# learning.net
KiCad netlist of a schematic drawn in EAGLE
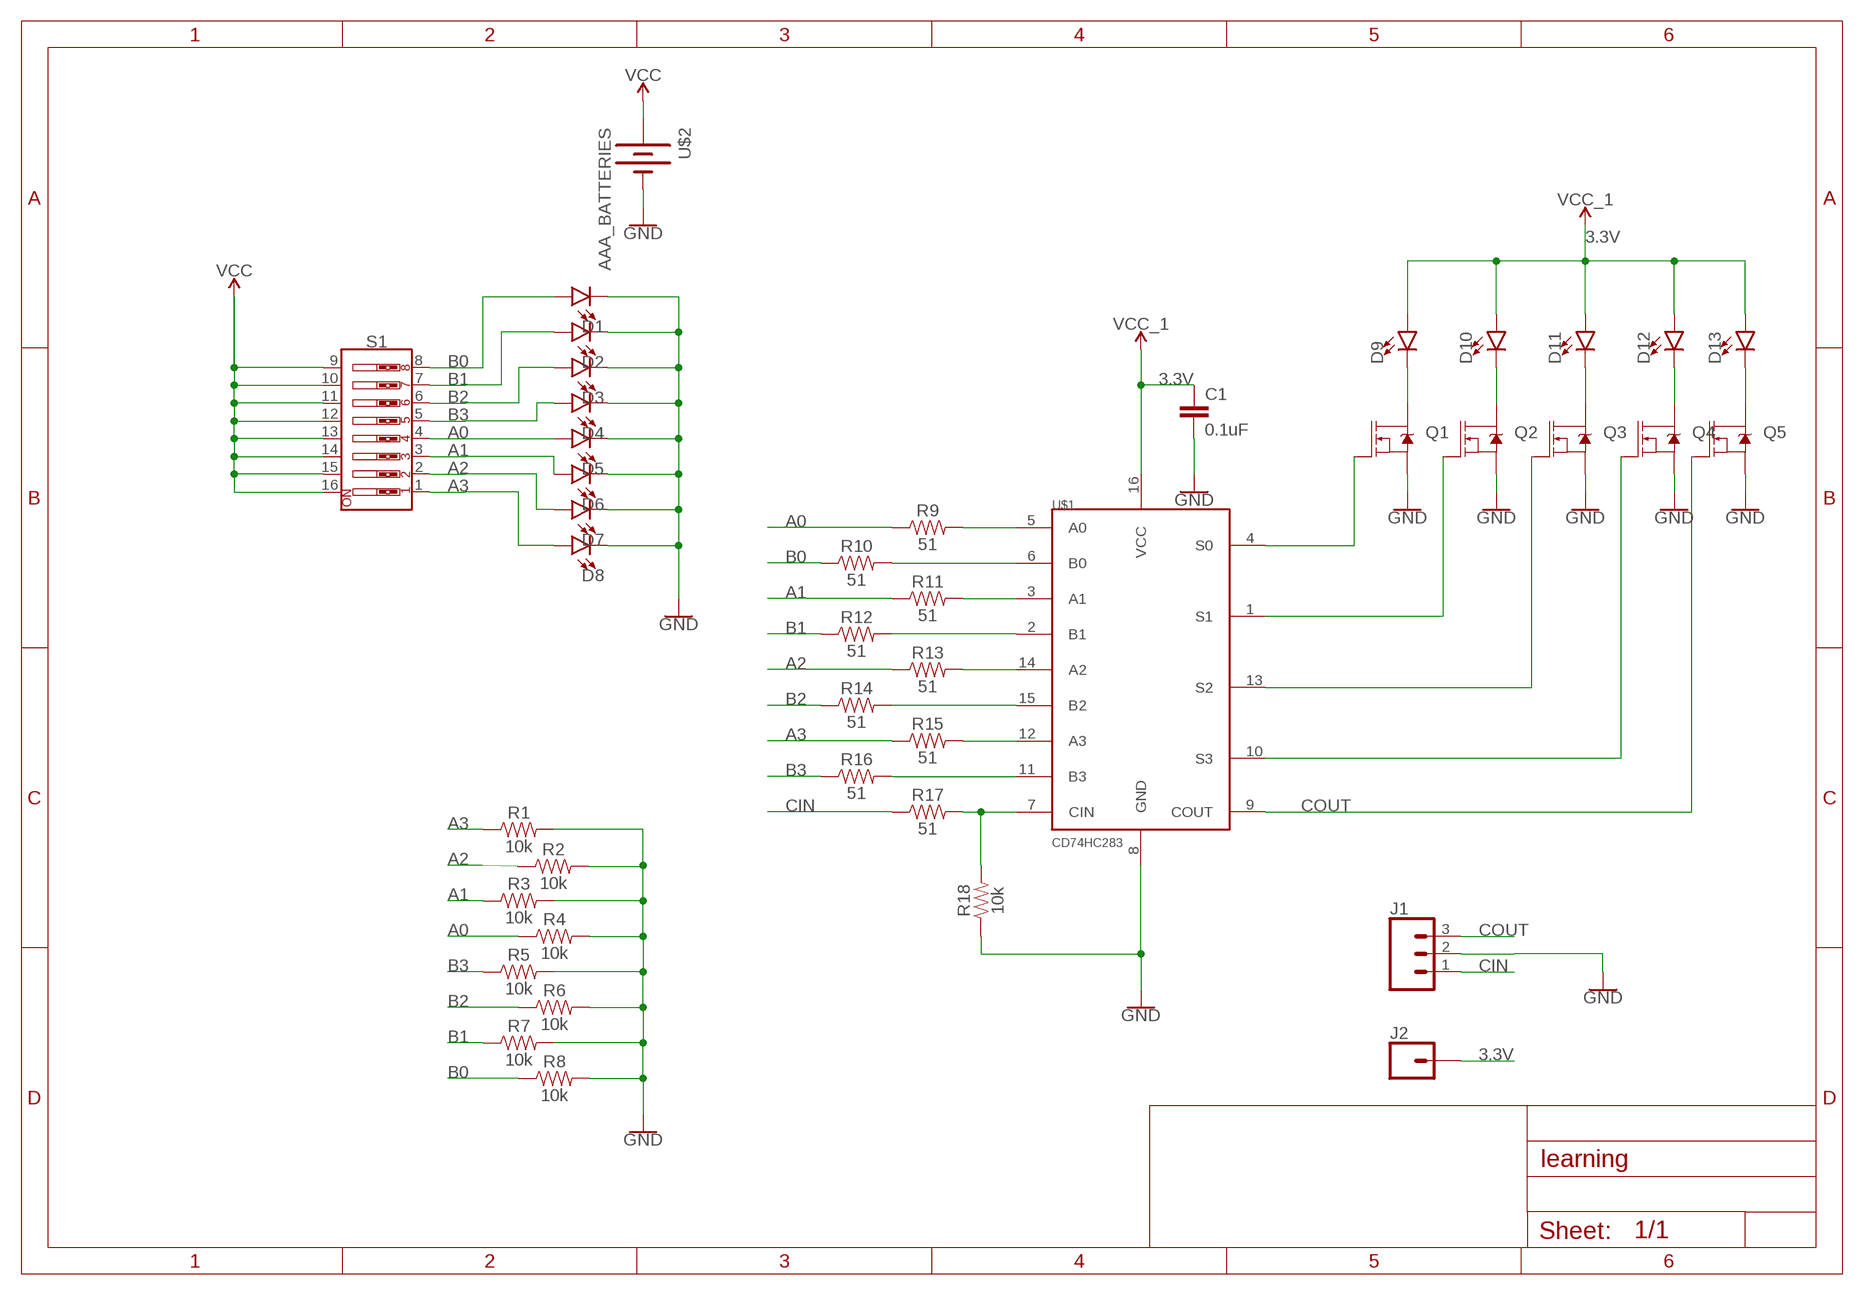
[diagram p0: schematic, sheet 1]

(export (version "E")
  (design (tool "Eeschema 10.0.6"))
  (components
    (comp (ref "C1")
      (value "0.1uF")
      (footprint "eagle-import:0603")
      (libsource (lib "eagle-import") (part "0.1UF-0603-25V-5%"))
    )
    (comp (ref "D1")
      (value "LED5MM")
      (footprint "eagle-import:LED_5MM")
      (libsource (lib "eagle-import") (part "LED5MM"))
    )
    (comp (ref "D2")
      (value "LED5MM")
      (footprint "eagle-import:LED_5MM")
      (libsource (lib "eagle-import") (part "LED5MM"))
    )
    (comp (ref "D3")
      (value "LED5MM")
      (footprint "eagle-import:LED_5MM")
      (libsource (lib "eagle-import") (part "LED5MM"))
    )
    (comp (ref "D4")
      (value "LED5MM")
      (footprint "eagle-import:LED_5MM")
      (libsource (lib "eagle-import") (part "LED5MM"))
    )
    (comp (ref "D5")
      (value "LED5MM")
      (footprint "eagle-import:LED_5MM")
      (libsource (lib "eagle-import") (part "LED5MM"))
    )
    (comp (ref "D6")
      (value "LED5MM")
      (footprint "eagle-import:LED_5MM")
      (libsource (lib "eagle-import") (part "LED5MM"))
    )
    (comp (ref "D7")
      (value "LED5MM")
      (footprint "eagle-import:LED_5MM")
      (libsource (lib "eagle-import") (part "LED5MM"))
    )
    (comp (ref "D8")
      (value "LED5MM")
      (footprint "eagle-import:LED_5MM")
      (libsource (lib "eagle-import") (part "LED5MM"))
    )
    (comp (ref "D9")
      (value "LED5MM")
      (footprint "eagle-import:LED_5MM")
      (libsource (lib "eagle-import") (part "LED5MM"))
    )
    (comp (ref "D10")
      (value "LED5MM")
      (footprint "eagle-import:LED_5MM")
      (libsource (lib "eagle-import") (part "LED5MM"))
    )
    (comp (ref "D11")
      (value "LED5MM")
      (footprint "eagle-import:LED_5MM")
      (libsource (lib "eagle-import") (part "LED5MM"))
    )
    (comp (ref "D12")
      (value "LED5MM")
      (footprint "eagle-import:LED_5MM")
      (libsource (lib "eagle-import") (part "LED5MM"))
    )
    (comp (ref "D13")
      (value "LED5MM")
      (footprint "eagle-import:LED_5MM")
      (libsource (lib "eagle-import") (part "LED5MM"))
    )
    (comp (ref "J1")
      (value "CONN_03")
      (footprint "eagle-import:1X03")
      (libsource (lib "eagle-import") (part "CONN_03"))
    )
    (comp (ref "J2")
      (value "CONN_01")
      (footprint "eagle-import:1X01")
      (libsource (lib "eagle-import") (part "CONN_01"))
    )
    (comp (ref "Q1")
      (value "MOSFET-NCH-BSS138")
      (footprint "eagle-import:SOT23-3")
      (libsource (lib "eagle-import") (part "MOSFET-NCH-BSS138"))
    )
    (comp (ref "Q2")
      (value "MOSFET-NCH-BSS138")
      (footprint "eagle-import:SOT23-3")
      (libsource (lib "eagle-import") (part "MOSFET-NCH-BSS138"))
    )
    (comp (ref "Q3")
      (value "MOSFET-NCH-BSS138")
      (footprint "eagle-import:SOT23-3")
      (libsource (lib "eagle-import") (part "MOSFET-NCH-BSS138"))
    )
    (comp (ref "Q4")
      (value "MOSFET-NCH-BSS138")
      (footprint "eagle-import:SOT23-3")
      (libsource (lib "eagle-import") (part "MOSFET-NCH-BSS138"))
    )
    (comp (ref "Q5")
      (value "MOSFET-NCH-BSS138")
      (footprint "eagle-import:SOT23-3")
      (libsource (lib "eagle-import") (part "MOSFET-NCH-BSS138"))
    )
    (comp (ref "R1")
      (value "10k")
      (footprint "eagle-import:0603")
      (libsource (lib "eagle-import") (part "RESISTOR0603"))
    )
    (comp (ref "R2")
      (value "10k")
      (footprint "eagle-import:0603")
      (libsource (lib "eagle-import") (part "RESISTOR0603"))
    )
    (comp (ref "R3")
      (value "10k")
      (footprint "eagle-import:0603")
      (libsource (lib "eagle-import") (part "RESISTOR0603"))
    )
    (comp (ref "R4")
      (value "10k")
      (footprint "eagle-import:0603")
      (libsource (lib "eagle-import") (part "RESISTOR0603"))
    )
    (comp (ref "R5")
      (value "10k")
      (footprint "eagle-import:0603")
      (libsource (lib "eagle-import") (part "RESISTOR0603"))
    )
    (comp (ref "R6")
      (value "10k")
      (footprint "eagle-import:0603")
      (libsource (lib "eagle-import") (part "RESISTOR0603"))
    )
    (comp (ref "R7")
      (value "10k")
      (footprint "eagle-import:0603")
      (libsource (lib "eagle-import") (part "RESISTOR0603"))
    )
    (comp (ref "R8")
      (value "10k")
      (footprint "eagle-import:0603")
      (libsource (lib "eagle-import") (part "RESISTOR0603"))
    )
    (comp (ref "R9")
      (value "51")
      (footprint "eagle-import:0603")
      (libsource (lib "eagle-import") (part "RESISTOR0603"))
    )
    (comp (ref "R10")
      (value "51")
      (footprint "eagle-import:0603")
      (libsource (lib "eagle-import") (part "RESISTOR0603"))
    )
    (comp (ref "R11")
      (value "51")
      (footprint "eagle-import:0603")
      (libsource (lib "eagle-import") (part "RESISTOR0603"))
    )
    (comp (ref "R12")
      (value "51")
      (footprint "eagle-import:0603")
      (libsource (lib "eagle-import") (part "RESISTOR0603"))
    )
    (comp (ref "R13")
      (value "51")
      (footprint "eagle-import:0603")
      (libsource (lib "eagle-import") (part "RESISTOR0603"))
    )
    (comp (ref "R14")
      (value "51")
      (footprint "eagle-import:0603")
      (libsource (lib "eagle-import") (part "RESISTOR0603"))
    )
    (comp (ref "R15")
      (value "51")
      (footprint "eagle-import:0603")
      (libsource (lib "eagle-import") (part "RESISTOR0603"))
    )
    (comp (ref "R16")
      (value "51")
      (footprint "eagle-import:0603")
      (libsource (lib "eagle-import") (part "RESISTOR0603"))
    )
    (comp (ref "R17")
      (value "51")
      (footprint "eagle-import:0603")
      (libsource (lib "eagle-import") (part "RESISTOR0603"))
    )
    (comp (ref "R18")
      (value "10k")
      (footprint "eagle-import:0603")
      (libsource (lib "eagle-import") (part "RESISTOR0603"))
    )
    (comp (ref "S1")
      (value "DIP-08-PTH")
      (footprint "eagle-import:DIPSWITCH-08")
      (libsource (lib "eagle-import") (part "DIP-08-PTH"))
    )
    (comp (ref "U$1")
      (value "CD74HC283")
      (footprint "eagle-import:SO016")
      (libsource (lib "eagle-import") (part "CD74HC283"))
    )
    (comp (ref "U$2")
      (value "AAA_BATTERIES")
      (footprint "eagle-import:WIRE_LEADS")
      (libsource (lib "eagle-import") (part "AAA_BATTERIES"))
    )
  )
  (nets
    (net (code "1") (name "/A0") (class "Default")
      (node (ref "D5") (pin "A") (pinfunction "A_A") (pintype "passive"))
      (node (ref "R4") (pin "1") (pinfunction "1_1") (pintype "passive"))
      (node (ref "R9") (pin "1") (pinfunction "1_1") (pintype "passive"))
      (node (ref "S1") (pin "4") (pinfunction "4_4") (pintype "passive"))
    )
    (net (code "2") (name "/A1") (class "Default")
      (node (ref "D6") (pin "A") (pinfunction "A_A") (pintype "passive"))
      (node (ref "R11") (pin "1") (pinfunction "1_1") (pintype "passive"))
      (node (ref "R3") (pin "1") (pinfunction "1_1") (pintype "passive"))
      (node (ref "S1") (pin "3") (pinfunction "3_3") (pintype "passive"))
    )
    (net (code "3") (name "/A2") (class "Default")
      (node (ref "D7") (pin "A") (pinfunction "A_A") (pintype "passive"))
      (node (ref "R13") (pin "1") (pinfunction "1_1") (pintype "passive"))
      (node (ref "R2") (pin "1") (pinfunction "1_1") (pintype "passive"))
      (node (ref "S1") (pin "2") (pinfunction "2_2") (pintype "passive"))
    )
    (net (code "4") (name "/A3") (class "Default")
      (node (ref "D8") (pin "A") (pinfunction "A_A") (pintype "passive"))
      (node (ref "R1") (pin "1") (pinfunction "1_1") (pintype "passive"))
      (node (ref "R15") (pin "1") (pinfunction "1_1") (pintype "passive"))
      (node (ref "S1") (pin "1") (pinfunction "1_1") (pintype "passive"))
    )
    (net (code "5") (name "/B0") (class "Default")
      (node (ref "D1") (pin "A") (pinfunction "A_A") (pintype "passive"))
      (node (ref "R10") (pin "1") (pinfunction "1_1") (pintype "passive"))
      (node (ref "R8") (pin "1") (pinfunction "1_1") (pintype "passive"))
      (node (ref "S1") (pin "8") (pinfunction "8_8") (pintype "passive"))
    )
    (net (code "6") (name "/B1") (class "Default")
      (node (ref "D2") (pin "A") (pinfunction "A_A") (pintype "passive"))
      (node (ref "R12") (pin "1") (pinfunction "1_1") (pintype "passive"))
      (node (ref "R7") (pin "1") (pinfunction "1_1") (pintype "passive"))
      (node (ref "S1") (pin "7") (pinfunction "7_7") (pintype "passive"))
    )
    (net (code "7") (name "/B2") (class "Default")
      (node (ref "D3") (pin "A") (pinfunction "A_A") (pintype "passive"))
      (node (ref "R14") (pin "1") (pinfunction "1_1") (pintype "passive"))
      (node (ref "R6") (pin "1") (pinfunction "1_1") (pintype "passive"))
      (node (ref "S1") (pin "6") (pinfunction "6_6") (pintype "passive"))
    )
    (net (code "8") (name "/B3") (class "Default")
      (node (ref "D4") (pin "A") (pinfunction "A_A") (pintype "passive"))
      (node (ref "R16") (pin "1") (pinfunction "1_1") (pintype "passive"))
      (node (ref "R5") (pin "1") (pinfunction "1_1") (pintype "passive"))
      (node (ref "S1") (pin "5") (pinfunction "5_5") (pintype "passive"))
    )
    (net (code "9") (name "/CIN") (class "Default")
      (node (ref "J1") (pin "1") (pinfunction "1_1") (pintype "passive"))
      (node (ref "R17") (pin "1") (pinfunction "1_1") (pintype "passive"))
    )
    (net (code "10") (name "/COUT") (class "Default")
      (node (ref "J1") (pin "3") (pinfunction "3_3") (pintype "passive"))
      (node (ref "Q5") (pin "1") (pinfunction "G_1") (pintype "bidirectional"))
      (node (ref "U$1") (pin "9") (pinfunction "COUT_9") (pintype "bidirectional"))
    )
    (net (code "11") (name "GND") (class "Default")
      (node (ref "C1") (pin "2") (pinfunction "2_2") (pintype "passive"))
      (node (ref "D1") (pin "K") (pinfunction "C_K") (pintype "passive"))
      (node (ref "D2") (pin "K") (pinfunction "C_K") (pintype "passive"))
      (node (ref "D3") (pin "K") (pinfunction "C_K") (pintype "passive"))
      (node (ref "D4") (pin "K") (pinfunction "C_K") (pintype "passive"))
      (node (ref "D5") (pin "K") (pinfunction "C_K") (pintype "passive"))
      (node (ref "D6") (pin "K") (pinfunction "C_K") (pintype "passive"))
      (node (ref "D7") (pin "K") (pinfunction "C_K") (pintype "passive"))
      (node (ref "D8") (pin "K") (pinfunction "C_K") (pintype "passive"))
      (node (ref "J1") (pin "2") (pinfunction "2_2") (pintype "passive"))
      (node (ref "Q1") (pin "2") (pinfunction "S_2") (pintype "bidirectional"))
      (node (ref "Q2") (pin "2") (pinfunction "S_2") (pintype "bidirectional"))
      (node (ref "Q3") (pin "2") (pinfunction "S_2") (pintype "bidirectional"))
      (node (ref "Q4") (pin "2") (pinfunction "S_2") (pintype "bidirectional"))
      (node (ref "Q5") (pin "2") (pinfunction "S_2") (pintype "bidirectional"))
      (node (ref "R1") (pin "2") (pinfunction "2_2") (pintype "passive"))
      (node (ref "R18") (pin "1") (pinfunction "1_1") (pintype "passive"))
      (node (ref "R2") (pin "2") (pinfunction "2_2") (pintype "passive"))
      (node (ref "R3") (pin "2") (pinfunction "2_2") (pintype "passive"))
      (node (ref "R4") (pin "2") (pinfunction "2_2") (pintype "passive"))
      (node (ref "R5") (pin "2") (pinfunction "2_2") (pintype "passive"))
      (node (ref "R6") (pin "2") (pinfunction "2_2") (pintype "passive"))
      (node (ref "R7") (pin "2") (pinfunction "2_2") (pintype "passive"))
      (node (ref "R8") (pin "2") (pinfunction "2_2") (pintype "passive"))
      (node (ref "U$1") (pin "8") (pinfunction "GND_8") (pintype "bidirectional"))
      (node (ref "U$2") (pin "P$1") (pinfunction "-_P$1") (pintype "power_in"))
    )
    (net (code "12") (name "Net-(D9-C)") (class "Default")
      (node (ref "D9") (pin "K") (pinfunction "C_K") (pintype "passive"))
      (node (ref "Q1") (pin "3") (pinfunction "D_3") (pintype "bidirectional"))
    )
    (net (code "13") (name "Net-(D10-C)") (class "Default")
      (node (ref "D10") (pin "K") (pinfunction "C_K") (pintype "passive"))
      (node (ref "Q2") (pin "3") (pinfunction "D_3") (pintype "bidirectional"))
    )
    (net (code "14") (name "Net-(D11-C)") (class "Default")
      (node (ref "D11") (pin "K") (pinfunction "C_K") (pintype "passive"))
      (node (ref "Q3") (pin "3") (pinfunction "D_3") (pintype "bidirectional"))
    )
    (net (code "15") (name "Net-(D12-C)") (class "Default")
      (node (ref "D12") (pin "K") (pinfunction "C_K") (pintype "passive"))
      (node (ref "Q4") (pin "3") (pinfunction "D_3") (pintype "bidirectional"))
    )
    (net (code "16") (name "Net-(D13-C)") (class "Default")
      (node (ref "D13") (pin "K") (pinfunction "C_K") (pintype "passive"))
      (node (ref "Q5") (pin "3") (pinfunction "D_3") (pintype "bidirectional"))
    )
    (net (code "17") (name "Net-(Q1-G)") (class "Default")
      (node (ref "Q1") (pin "1") (pinfunction "G_1") (pintype "bidirectional"))
      (node (ref "U$1") (pin "4") (pinfunction "S0_4") (pintype "bidirectional"))
    )
    (net (code "18") (name "Net-(Q2-G)") (class "Default")
      (node (ref "Q2") (pin "1") (pinfunction "G_1") (pintype "bidirectional"))
      (node (ref "U$1") (pin "1") (pinfunction "S1_1") (pintype "bidirectional"))
    )
    (net (code "19") (name "Net-(Q3-G)") (class "Default")
      (node (ref "Q3") (pin "1") (pinfunction "G_1") (pintype "bidirectional"))
      (node (ref "U$1") (pin "13") (pinfunction "S2_13") (pintype "bidirectional"))
    )
    (net (code "20") (name "Net-(Q4-G)") (class "Default")
      (node (ref "Q4") (pin "1") (pinfunction "G_1") (pintype "bidirectional"))
      (node (ref "U$1") (pin "10") (pinfunction "S3_10") (pintype "bidirectional"))
    )
    (net (code "21") (name "Net-(U$1-A0)") (class "Default")
      (node (ref "R9") (pin "2") (pinfunction "2_2") (pintype "passive"))
      (node (ref "U$1") (pin "5") (pinfunction "A0_5") (pintype "bidirectional"))
    )
    (net (code "22") (name "Net-(U$1-A1)") (class "Default")
      (node (ref "R11") (pin "2") (pinfunction "2_2") (pintype "passive"))
      (node (ref "U$1") (pin "3") (pinfunction "A1_3") (pintype "bidirectional"))
    )
    (net (code "23") (name "Net-(U$1-A2)") (class "Default")
      (node (ref "R13") (pin "2") (pinfunction "2_2") (pintype "passive"))
      (node (ref "U$1") (pin "14") (pinfunction "A2_14") (pintype "bidirectional"))
    )
    (net (code "24") (name "Net-(U$1-A3)") (class "Default")
      (node (ref "R15") (pin "2") (pinfunction "2_2") (pintype "passive"))
      (node (ref "U$1") (pin "12") (pinfunction "A3_12") (pintype "bidirectional"))
    )
    (net (code "25") (name "Net-(U$1-B0)") (class "Default")
      (node (ref "R10") (pin "2") (pinfunction "2_2") (pintype "passive"))
      (node (ref "U$1") (pin "6") (pinfunction "B0_6") (pintype "bidirectional"))
    )
    (net (code "26") (name "Net-(U$1-B1)") (class "Default")
      (node (ref "R12") (pin "2") (pinfunction "2_2") (pintype "passive"))
      (node (ref "U$1") (pin "2") (pinfunction "B1_2") (pintype "bidirectional"))
    )
    (net (code "27") (name "Net-(U$1-B2)") (class "Default")
      (node (ref "R14") (pin "2") (pinfunction "2_2") (pintype "passive"))
      (node (ref "U$1") (pin "15") (pinfunction "B2_15") (pintype "bidirectional"))
    )
    (net (code "28") (name "Net-(U$1-B3)") (class "Default")
      (node (ref "R16") (pin "2") (pinfunction "2_2") (pintype "passive"))
      (node (ref "U$1") (pin "11") (pinfunction "B3_11") (pintype "bidirectional"))
    )
    (net (code "29") (name "Net-(U$1-CIN)") (class "Default")
      (node (ref "R17") (pin "2") (pinfunction "2_2") (pintype "passive"))
      (node (ref "R18") (pin "2") (pinfunction "2_2") (pintype "passive"))
      (node (ref "U$1") (pin "7") (pinfunction "CIN_7") (pintype "bidirectional"))
    )
    (net (code "30") (name "VCC") (class "Default")
      (node (ref "S1") (pin "10") (pinfunction "10_10") (pintype "passive"))
      (node (ref "S1") (pin "11") (pinfunction "11_11") (pintype "passive"))
      (node (ref "S1") (pin "12") (pinfunction "12_12") (pintype "passive"))
      (node (ref "S1") (pin "13") (pinfunction "13_13") (pintype "passive"))
      (node (ref "S1") (pin "14") (pinfunction "14_14") (pintype "passive"))
      (node (ref "S1") (pin "15") (pinfunction "15_15") (pintype "passive"))
      (node (ref "S1") (pin "16") (pinfunction "16_16") (pintype "passive"))
      (node (ref "S1") (pin "9") (pinfunction "9_9") (pintype "passive"))
      (node (ref "U$2") (pin "P$2") (pinfunction "+_P$2") (pintype "power_in"))
    )
    (net (code "31") (name "VCC_1") (class "Default")
      (node (ref "C1") (pin "1") (pinfunction "1_1") (pintype "passive"))
      (node (ref "D10") (pin "A") (pinfunction "A_A") (pintype "passive"))
      (node (ref "D11") (pin "A") (pinfunction "A_A") (pintype "passive"))
      (node (ref "D12") (pin "A") (pinfunction "A_A") (pintype "passive"))
      (node (ref "D13") (pin "A") (pinfunction "A_A") (pintype "passive"))
      (node (ref "D9") (pin "A") (pinfunction "A_A") (pintype "passive"))
      (node (ref "J2") (pin "1") (pinfunction "1_1") (pintype "passive"))
      (node (ref "U$1") (pin "16") (pinfunction "VCC_16") (pintype "bidirectional"))
    )
  )
)
